# rx_sensor.net
KiCad netlist of a schematic drawn in EAGLE
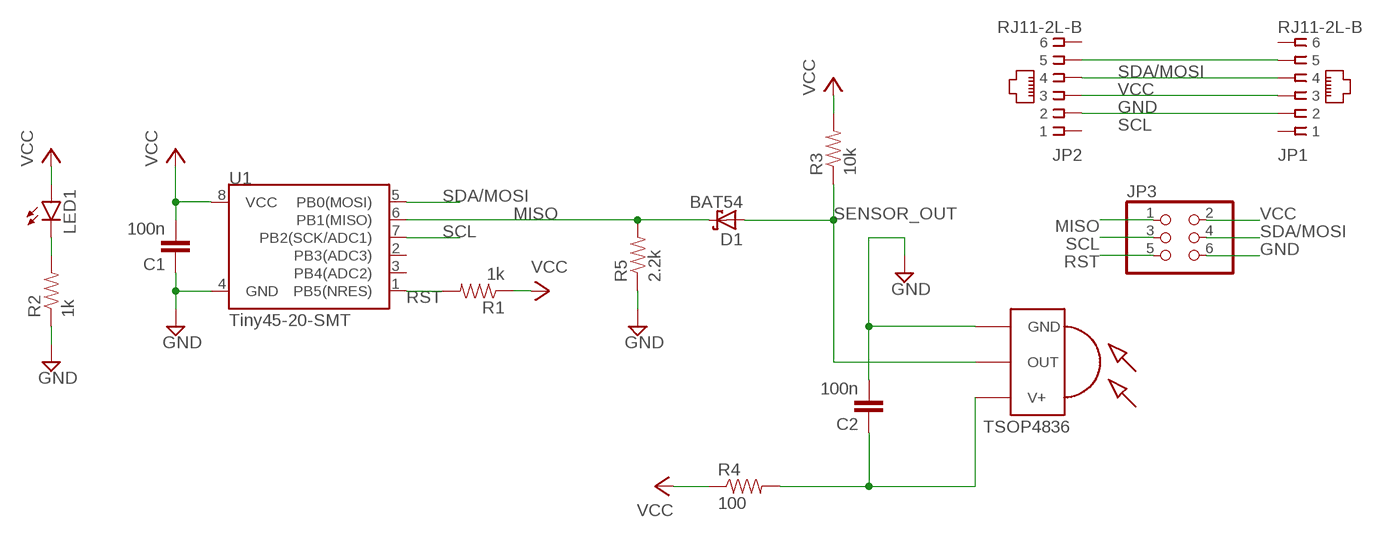
[diagram p0: schematic, sheet 1]

(export (version "E")
  (design (tool "Eeschema 10.0.6"))
  (components
    (comp (ref "C1")
      (value "100n")
      (footprint "eagle-import:0603-CAP")
      (libsource (lib "eagle-import") (part "CAP0603-CAP"))
    )
    (comp (ref "C2")
      (value "100n")
      (footprint "eagle-import:0603-CAP")
      (libsource (lib "eagle-import") (part "CAP0603-CAP"))
    )
    (comp (ref "D1")
      (value "BAT54")
      (footprint "eagle-import:SOT23")
      (libsource (lib "eagle-import") (part "BAT54"))
    )
    (comp (ref "JP1")
      (value "RJ11-2L-B")
      (footprint "eagle-import:RJ11-NO_SHIELD")
      (fields (field (name "MF") "TYCO ELECTRONICS"))
      (libsource (lib "eagle-import") (part "RJ11-2L-B"))
    )
    (comp (ref "JP2")
      (value "RJ11-2L-B")
      (footprint "eagle-import:RJ11-NO_SHIELD")
      (fields (field (name "MF") "TYCO ELECTRONICS"))
      (libsource (lib "eagle-import") (part "RJ11-2L-B"))
    )
    (comp (ref "JP3")
      (value "PINHD-2X3")
      (footprint "eagle-import:2X03")
      (libsource (lib "eagle-import") (part "PINHD-2X3"))
    )
    (comp (ref "LED1")
      (value "LED0603")
      (footprint "eagle-import:LED-0603")
      (libsource (lib "eagle-import") (part "LED0603"))
    )
    (comp (ref "R1")
      (value "1k")
      (footprint "eagle-import:0603-RES")
      (libsource (lib "eagle-import") (part "RESISTOR0603"))
    )
    (comp (ref "R2")
      (value "1k")
      (footprint "eagle-import:0603-RES")
      (libsource (lib "eagle-import") (part "RESISTOR0603"))
    )
    (comp (ref "R3")
      (value "10k")
      (footprint "eagle-import:0603-RES")
      (libsource (lib "eagle-import") (part "RESISTOR0603"))
    )
    (comp (ref "R4")
      (value "100")
      (footprint "eagle-import:0603-RES")
      (libsource (lib "eagle-import") (part "RESISTOR0603"))
    )
    (comp (ref "R5")
      (value "2.2k")
      (footprint "eagle-import:0603-RES")
      (libsource (lib "eagle-import") (part "RESISTOR0603"))
    )
    (comp (ref "TSOP4836")
      (value "TSOP4836")
      (footprint "eagle-import:TSOP18XX")
      (libsource (lib "eagle-import") (part "TSOP4836"))
    )
    (comp (ref "U1")
      (value "Tiny45-20-SMT")
      (footprint "eagle-import:SO08-EIAJ")
      (libsource (lib "eagle-import") (part "ATTINY45TINY45-20-SMT"))
    )
  )
  (nets
    (net (code "1") (name "/MISO") (class "Default")
      (node (ref "D1") (pin "3") (pinfunction "C_3") (pintype "passive"))
      (node (ref "JP3") (pin "1") (pinfunction "1_1") (pintype "passive"))
      (node (ref "R5") (pin "2") (pinfunction "2_2") (pintype "passive"))
      (node (ref "U1") (pin "6") (pinfunction "PB1(MISO)_6") (pintype "bidirectional"))
    )
    (net (code "2") (name "/RST") (class "Default")
      (node (ref "JP3") (pin "5") (pinfunction "5_5") (pintype "passive"))
      (node (ref "R1") (pin "2") (pinfunction "2_2") (pintype "passive"))
      (node (ref "U1") (pin "1") (pinfunction "PB5(NRES)_1") (pintype "bidirectional"))
    )
    (net (code "3") (name "/SCL") (class "Default")
      (node (ref "JP1") (pin "2") (pinfunction "2_2") (pintype "passive"))
      (node (ref "JP2") (pin "2") (pinfunction "2_2") (pintype "passive"))
      (node (ref "JP3") (pin "3") (pinfunction "3_3") (pintype "passive"))
      (node (ref "U1") (pin "7") (pinfunction "PB2(SCK/ADC1)_7") (pintype "bidirectional"))
    )
    (net (code "4") (name "/SDA{slash}MOSI") (class "Default")
      (node (ref "JP1") (pin "5") (pinfunction "5_5") (pintype "passive"))
      (node (ref "JP2") (pin "5") (pinfunction "5_5") (pintype "passive"))
      (node (ref "JP3") (pin "4") (pinfunction "4_4") (pintype "passive"))
      (node (ref "U1") (pin "5") (pinfunction "PB0(MOSI)_5") (pintype "bidirectional"))
    )
    (net (code "5") (name "/SENSOR_OUT") (class "Default")
      (node (ref "D1") (pin "1") (pinfunction "A_1") (pintype "passive"))
      (node (ref "R3") (pin "1") (pinfunction "1_1") (pintype "passive"))
      (node (ref "TSOP4836") (pin "OUT") (pinfunction "OUT_OUT") (pintype "bidirectional"))
    )
    (net (code "6") (name "GND") (class "Default")
      (node (ref "C1") (pin "1") (pinfunction "1_1") (pintype "passive"))
      (node (ref "C2") (pin "2") (pinfunction "2_2") (pintype "passive"))
      (node (ref "JP1") (pin "3") (pinfunction "3_3") (pintype "passive"))
      (node (ref "JP2") (pin "3") (pinfunction "3_3") (pintype "passive"))
      (node (ref "JP3") (pin "6") (pinfunction "6_6") (pintype "passive"))
      (node (ref "R2") (pin "1") (pinfunction "1_1") (pintype "passive"))
      (node (ref "R5") (pin "1") (pinfunction "1_1") (pintype "passive"))
      (node (ref "TSOP4836") (pin "GND") (pinfunction "GND_GND") (pintype "bidirectional"))
      (node (ref "U1") (pin "4") (pinfunction "GND_4") (pintype "bidirectional"))
    )
    (net (code "7") (name "Net-(LED1-PadC)") (class "Default")
      (node (ref "LED1") (pin "C") (pinfunction "C_C") (pintype "passive"))
      (node (ref "R2") (pin "2") (pinfunction "2_2") (pintype "passive"))
    )
    (net (code "8") (name "Net-(TSOP4836-V+)") (class "Default")
      (node (ref "C2") (pin "1") (pinfunction "1_1") (pintype "passive"))
      (node (ref "R4") (pin "2") (pinfunction "2_2") (pintype "passive"))
      (node (ref "TSOP4836") (pin "VCC") (pinfunction "V+_VCC") (pintype "bidirectional"))
    )
    (net (code "9") (name "VCC") (class "Default")
      (node (ref "C1") (pin "2") (pinfunction "2_2") (pintype "passive"))
      (node (ref "JP1") (pin "4") (pinfunction "4_4") (pintype "passive"))
      (node (ref "JP2") (pin "4") (pinfunction "4_4") (pintype "passive"))
      (node (ref "JP3") (pin "2") (pinfunction "2_2") (pintype "passive"))
      (node (ref "LED1") (pin "A") (pinfunction "A_A") (pintype "passive"))
      (node (ref "R1") (pin "1") (pinfunction "1_1") (pintype "passive"))
      (node (ref "R3") (pin "2") (pinfunction "2_2") (pintype "passive"))
      (node (ref "R4") (pin "1") (pinfunction "1_1") (pintype "passive"))
      (node (ref "U1") (pin "8") (pinfunction "VCC_8") (pintype "bidirectional"))
    )
    (net (code "10") (name "unconnected-(JP1-Pad1)") (class "Default")
      (node (ref "JP1") (pin "1") (pinfunction "1_1") (pintype "passive"))
    )
    (net (code "11") (name "unconnected-(JP1-Pad6)") (class "Default")
      (node (ref "JP1") (pin "6") (pinfunction "6_6") (pintype "passive"))
    )
    (net (code "12") (name "unconnected-(JP2-Pad1)") (class "Default")
      (node (ref "JP2") (pin "1") (pinfunction "1_1") (pintype "passive"))
    )
    (net (code "13") (name "unconnected-(JP2-Pad6)") (class "Default")
      (node (ref "JP2") (pin "6") (pinfunction "6_6") (pintype "passive"))
    )
    (net (code "14") (name "unconnected-(U1-PB3(ADC3)-Pad2)") (class "Default")
      (node (ref "U1") (pin "2") (pinfunction "PB3(ADC3)_2") (pintype "bidirectional"))
    )
    (net (code "15") (name "unconnected-(U1-PB4(ADC2)-Pad3)") (class "Default")
      (node (ref "U1") (pin "3") (pinfunction "PB4(ADC2)_3") (pintype "bidirectional"))
    )
  )
)
